# Sheet1.net
KiCad netlist of a schematic drawn in Altium Designer
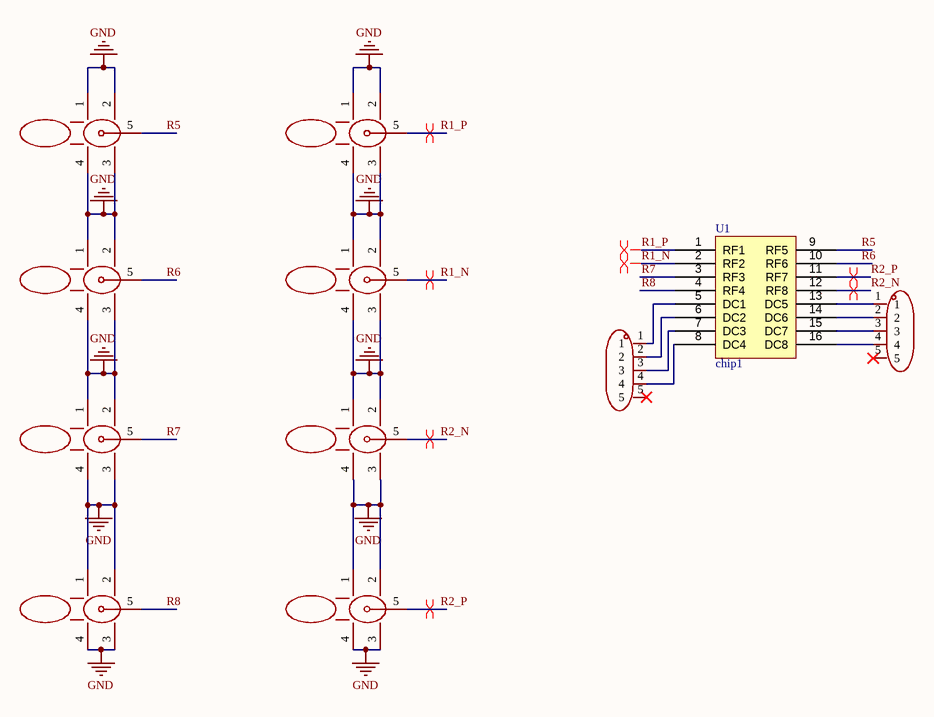
[diagram p0: Sheet1.SchDoc]

(export (version "E")
  (design (tool "Eeschema 10.0.6"))
  (components
    (comp (ref "H1")
      (value "PZ200V-11-05P")
      (footprint "HDR-TH_5P-P2.00-V-M")
      (fields (field (name "MANUFACTURER") "XFCN(兴飞)"))
      (libsource (lib "PZ200V-11-05P") (part "PZ200V-11-05P"))
    )
    (comp (ref "H2")
      (value "PZ200V-11-05P")
      (footprint "HDR-TH_5P-P2.00-V-M")
      (fields (field (name "MANUFACTURER") "XFCN(兴飞)"))
      (libsource (lib "PZ200V-11-05P") (part "PZ200V-11-05P"))
    )
    (comp (ref "RF1")
      (value "BWSMA-KE-Z001")
      (footprint "SMA-TH_BWSMA-KE-Z001")
      (fields (field (name "MANUFACTURER") "BAT WIRELESS(蝙蝠无线)"))
      (libsource (lib "BWSMA-KE-Z001") (part "BWSMA-KE-Z001_C496549"))
    )
    (comp (ref "RF2")
      (value "BWSMA-KE-Z001")
      (footprint "SMA-TH_BWSMA-KE-Z001")
      (fields (field (name "MANUFACTURER") "BAT WIRELESS(蝙蝠无线)"))
      (libsource (lib "BWSMA-KE-Z001") (part "BWSMA-KE-Z001_C496549"))
    )
    (comp (ref "RF3")
      (value "BWSMA-KE-Z001")
      (footprint "SMA-TH_BWSMA-KE-Z001")
      (fields (field (name "MANUFACTURER") "BAT WIRELESS(蝙蝠无线)"))
      (libsource (lib "BWSMA-KE-Z001") (part "BWSMA-KE-Z001_C496549"))
    )
    (comp (ref "RF4")
      (value "BWSMA-KE-Z001")
      (footprint "SMA-TH_BWSMA-KE-Z001")
      (fields (field (name "MANUFACTURER") "BAT WIRELESS(蝙蝠无线)"))
      (libsource (lib "BWSMA-KE-Z001") (part "BWSMA-KE-Z001_C496549"))
    )
    (comp (ref "RF5")
      (value "BWSMA-KE-Z001")
      (footprint "SMA-TH_BWSMA-KE-Z001")
      (fields (field (name "MANUFACTURER") "BAT WIRELESS(蝙蝠无线)"))
      (libsource (lib "BWSMA-KE-Z001") (part "BWSMA-KE-Z001_C496549"))
    )
    (comp (ref "RF6")
      (value "BWSMA-KE-Z001")
      (footprint "SMA-TH_BWSMA-KE-Z001")
      (fields (field (name "MANUFACTURER") "BAT WIRELESS(蝙蝠无线)"))
      (libsource (lib "BWSMA-KE-Z001") (part "BWSMA-KE-Z001_C496549"))
    )
    (comp (ref "RF7")
      (value "BWSMA-KE-Z001")
      (footprint "SMA-TH_BWSMA-KE-Z001")
      (fields (field (name "MANUFACTURER") "BAT WIRELESS(蝙蝠无线)"))
      (libsource (lib "BWSMA-KE-Z001") (part "BWSMA-KE-Z001_C496549"))
    )
    (comp (ref "RF8")
      (value "BWSMA-KE-Z001")
      (footprint "SMA-TH_BWSMA-KE-Z001")
      (fields (field (name "MANUFACTURER") "BAT WIRELESS(蝙蝠无线)"))
      (libsource (lib "BWSMA-KE-Z001") (part "BWSMA-KE-Z001_C496549"))
    )
    (comp (ref "U1") (value "chip1") (footprint "chip1") (libsource (lib "Schlib1") (part "chip1")))
  )
  (nets
    (net (code "1") (name "/R1_N") (class "Default")
      (node (ref "RF4") (pin "5") (pinfunction "5_5") (pintype "passive"))
      (node (ref "U1") (pin "2") (pinfunction "RF2_2") (pintype "passive"))
    )
    (net (code "2") (name "/R1_P") (class "Default")
      (node (ref "RF2") (pin "5") (pinfunction "5_5") (pintype "passive"))
      (node (ref "U1") (pin "1") (pinfunction "RF1_1") (pintype "passive"))
    )
    (net (code "3") (name "/R2_N") (class "Default")
      (node (ref "RF6") (pin "5") (pinfunction "5_5") (pintype "passive"))
      (node (ref "U1") (pin "12") (pinfunction "RF8_12") (pintype "passive"))
    )
    (net (code "4") (name "/R2_P") (class "Default")
      (node (ref "RF8") (pin "5") (pinfunction "5_5") (pintype "passive"))
      (node (ref "U1") (pin "11") (pinfunction "RF7_11") (pintype "passive"))
    )
    (net (code "5") (name "/R5") (class "Default")
      (node (ref "RF1") (pin "5") (pinfunction "5_5") (pintype "passive"))
      (node (ref "U1") (pin "9") (pinfunction "RF5_9") (pintype "passive"))
    )
    (net (code "6") (name "/R6") (class "Default")
      (node (ref "RF3") (pin "5") (pinfunction "5_5") (pintype "passive"))
      (node (ref "U1") (pin "10") (pinfunction "RF6_10") (pintype "passive"))
    )
    (net (code "7") (name "/R7") (class "Default")
      (node (ref "RF5") (pin "5") (pinfunction "5_5") (pintype "passive"))
      (node (ref "U1") (pin "3") (pinfunction "RF3_3") (pintype "passive"))
    )
    (net (code "8") (name "/R8") (class "Default")
      (node (ref "RF7") (pin "5") (pinfunction "5_5") (pintype "passive"))
      (node (ref "U1") (pin "4") (pinfunction "RF4_4") (pintype "passive"))
    )
    (net (code "9") (name "GND") (class "Default")
      (node (ref "RF1") (pin "1") (pinfunction "1_1") (pintype "passive"))
      (node (ref "RF1") (pin "2") (pinfunction "2_2") (pintype "passive"))
      (node (ref "RF1") (pin "3") (pinfunction "3_3") (pintype "passive"))
      (node (ref "RF1") (pin "4") (pinfunction "4_4") (pintype "passive"))
      (node (ref "RF2") (pin "1") (pinfunction "1_1") (pintype "passive"))
      (node (ref "RF2") (pin "2") (pinfunction "2_2") (pintype "passive"))
      (node (ref "RF2") (pin "3") (pinfunction "3_3") (pintype "passive"))
      (node (ref "RF2") (pin "4") (pinfunction "4_4") (pintype "passive"))
      (node (ref "RF3") (pin "1") (pinfunction "1_1") (pintype "passive"))
      (node (ref "RF3") (pin "2") (pinfunction "2_2") (pintype "passive"))
      (node (ref "RF3") (pin "3") (pinfunction "3_3") (pintype "passive"))
      (node (ref "RF3") (pin "4") (pinfunction "4_4") (pintype "passive"))
      (node (ref "RF4") (pin "1") (pinfunction "1_1") (pintype "passive"))
      (node (ref "RF4") (pin "2") (pinfunction "2_2") (pintype "passive"))
      (node (ref "RF4") (pin "3") (pinfunction "3_3") (pintype "passive"))
      (node (ref "RF4") (pin "4") (pinfunction "4_4") (pintype "passive"))
      (node (ref "RF5") (pin "1") (pinfunction "1_1") (pintype "passive"))
      (node (ref "RF5") (pin "2") (pinfunction "2_2") (pintype "passive"))
      (node (ref "RF5") (pin "3") (pinfunction "3_3") (pintype "passive"))
      (node (ref "RF5") (pin "4") (pinfunction "4_4") (pintype "passive"))
      (node (ref "RF6") (pin "1") (pinfunction "1_1") (pintype "passive"))
      (node (ref "RF6") (pin "2") (pinfunction "2_2") (pintype "passive"))
      (node (ref "RF6") (pin "3") (pinfunction "3_3") (pintype "passive"))
      (node (ref "RF6") (pin "4") (pinfunction "4_4") (pintype "passive"))
      (node (ref "RF7") (pin "1") (pinfunction "1_1") (pintype "passive"))
      (node (ref "RF7") (pin "2") (pinfunction "2_2") (pintype "passive"))
      (node (ref "RF7") (pin "3") (pinfunction "3_3") (pintype "passive"))
      (node (ref "RF7") (pin "4") (pinfunction "4_4") (pintype "passive"))
      (node (ref "RF8") (pin "1") (pinfunction "1_1") (pintype "passive"))
      (node (ref "RF8") (pin "2") (pinfunction "2_2") (pintype "passive"))
      (node (ref "RF8") (pin "3") (pinfunction "3_3") (pintype "passive"))
      (node (ref "RF8") (pin "4") (pinfunction "4_4") (pintype "passive"))
    )
    (net (code "10") (name "Net-(U1-DC1)") (class "Default")
      (node (ref "H2") (pin "1") (pinfunction "1_1") (pintype "passive"))
      (node (ref "U1") (pin "5") (pinfunction "DC1_5") (pintype "passive"))
    )
    (net (code "11") (name "Net-(U1-DC2)") (class "Default")
      (node (ref "H2") (pin "2") (pinfunction "2_2") (pintype "passive"))
      (node (ref "U1") (pin "6") (pinfunction "DC2_6") (pintype "passive"))
    )
    (net (code "12") (name "Net-(U1-DC3)") (class "Default")
      (node (ref "H2") (pin "3") (pinfunction "3_3") (pintype "passive"))
      (node (ref "U1") (pin "7") (pinfunction "DC3_7") (pintype "passive"))
    )
    (net (code "13") (name "Net-(U1-DC4)") (class "Default")
      (node (ref "H2") (pin "4") (pinfunction "4_4") (pintype "passive"))
      (node (ref "U1") (pin "8") (pinfunction "DC4_8") (pintype "passive"))
    )
    (net (code "14") (name "Net-(U1-DC5)") (class "Default")
      (node (ref "H1") (pin "1") (pinfunction "1_1") (pintype "passive"))
      (node (ref "U1") (pin "13") (pinfunction "DC5_13") (pintype "passive"))
    )
    (net (code "15") (name "Net-(U1-DC6)") (class "Default")
      (node (ref "H1") (pin "2") (pinfunction "2_2") (pintype "passive"))
      (node (ref "U1") (pin "14") (pinfunction "DC6_14") (pintype "passive"))
    )
    (net (code "16") (name "Net-(U1-DC7)") (class "Default")
      (node (ref "H1") (pin "3") (pinfunction "3_3") (pintype "passive"))
      (node (ref "U1") (pin "15") (pinfunction "DC7_15") (pintype "passive"))
    )
    (net (code "17") (name "Net-(U1-DC8)") (class "Default")
      (node (ref "H1") (pin "4") (pinfunction "4_4") (pintype "passive"))
      (node (ref "U1") (pin "16") (pinfunction "DC8_16") (pintype "passive"))
    )
    (net (code "18") (name "unconnected-(H1-Pad5)") (class "Default")
      (node (ref "H1") (pin "5") (pinfunction "5_5") (pintype "passive+no_connect"))
    )
    (net (code "19") (name "unconnected-(H2-Pad5)") (class "Default")
      (node (ref "H2") (pin "5") (pinfunction "5_5") (pintype "passive+no_connect"))
    )
  )
)
